# SCH_EasyEDA_OpenComs_ABP1_Front-panel_20.net
KiCad netlist of a schematic drawn in EasyEDA
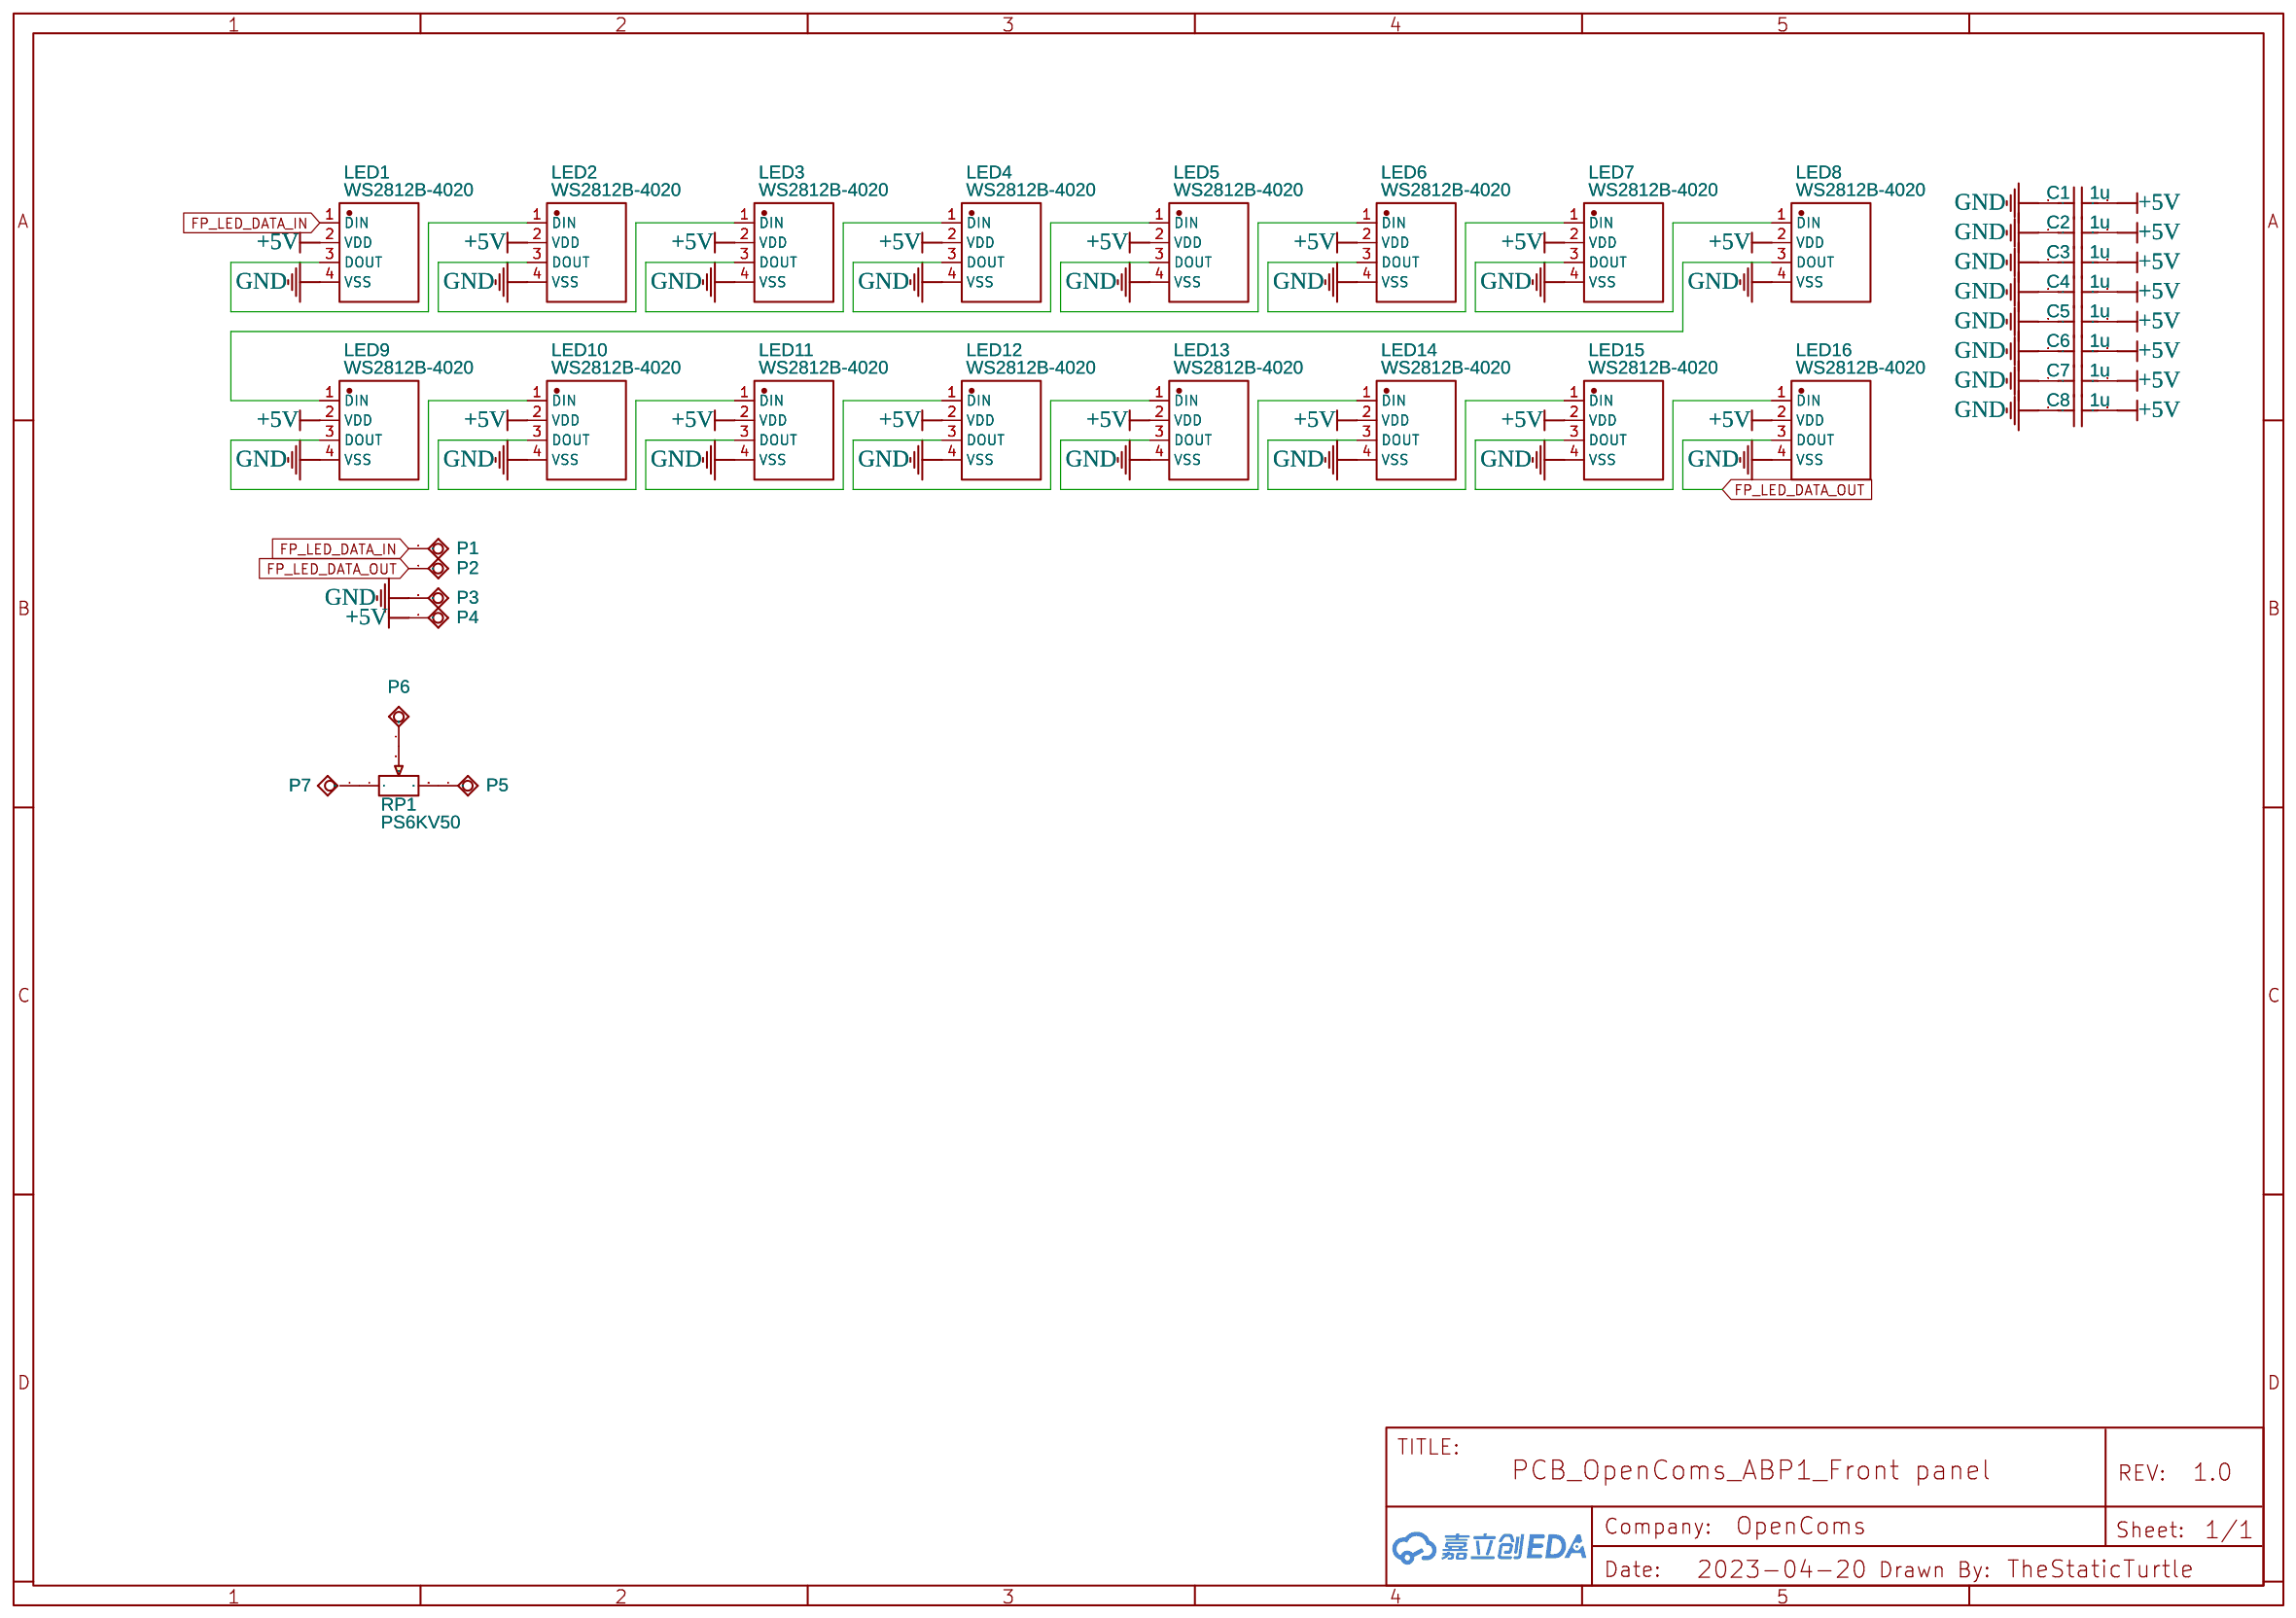
[diagram p0: schematic sheet]

(export (version "E")
  (design (tool "Eeschema 10.0.6"))
  (components
    (comp (ref "C1")
      (value "1u")
      (fields
        (field (name "BOM_Manufacturer Part") "CL21B105KBFNNNE")
        (field (name "BOM_Supplier Part") "C28323")
      )
      (libsource (lib "") (part "C_0805_US"))
    )
    (comp (ref "C2")
      (value "1u")
      (fields
        (field (name "BOM_Manufacturer Part") "CL21B105KBFNNNE")
        (field (name "BOM_Supplier Part") "C28323")
      )
      (libsource (lib "") (part "C_0805_US"))
    )
    (comp (ref "C3")
      (value "1u")
      (fields
        (field (name "BOM_Manufacturer Part") "CL21B105KBFNNNE")
        (field (name "BOM_Supplier Part") "C28323")
      )
      (libsource (lib "") (part "C_0805_US"))
    )
    (comp (ref "C4")
      (value "1u")
      (fields
        (field (name "BOM_Manufacturer Part") "CL21B105KBFNNNE")
        (field (name "BOM_Supplier Part") "C28323")
      )
      (libsource (lib "") (part "C_0805_US"))
    )
    (comp (ref "C5")
      (value "1u")
      (fields
        (field (name "BOM_Manufacturer Part") "CL21B105KBFNNNE")
        (field (name "BOM_Supplier Part") "C28323")
      )
      (libsource (lib "") (part "C_0805_US"))
    )
    (comp (ref "C6")
      (value "1u")
      (fields
        (field (name "BOM_Manufacturer Part") "CL21B105KBFNNNE")
        (field (name "BOM_Supplier Part") "C28323")
      )
      (libsource (lib "") (part "C_0805_US"))
    )
    (comp (ref "C7")
      (value "1u")
      (fields
        (field (name "BOM_Manufacturer Part") "CL21B105KBFNNNE")
        (field (name "BOM_Supplier Part") "C28323")
      )
      (libsource (lib "") (part "C_0805_US"))
    )
    (comp (ref "C8")
      (value "1u")
      (fields
        (field (name "BOM_Manufacturer Part") "CL21B105KBFNNNE")
        (field (name "BOM_Supplier Part") "C28323")
      )
      (libsource (lib "") (part "C_0805_US"))
    )
    (comp (ref "LED1")
      (value "WS2812B-4020")
      (fields (field (name "BOM_Supplier Part") "C965557"))
      (libsource (lib "") (part "WS2812B-4020"))
    )
    (comp (ref "LED2")
      (value "WS2812B-4020")
      (fields (field (name "BOM_Supplier Part") "C965557"))
      (libsource (lib "") (part "WS2812B-4020"))
    )
    (comp (ref "LED3")
      (value "WS2812B-4020")
      (fields (field (name "BOM_Supplier Part") "C965557"))
      (libsource (lib "") (part "WS2812B-4020"))
    )
    (comp (ref "LED4")
      (value "WS2812B-4020")
      (fields (field (name "BOM_Supplier Part") "C965557"))
      (libsource (lib "") (part "WS2812B-4020"))
    )
    (comp (ref "LED5")
      (value "WS2812B-4020")
      (fields (field (name "BOM_Supplier Part") "C965557"))
      (libsource (lib "") (part "WS2812B-4020"))
    )
    (comp (ref "LED6")
      (value "WS2812B-4020")
      (fields (field (name "BOM_Supplier Part") "C965557"))
      (libsource (lib "") (part "WS2812B-4020"))
    )
    (comp (ref "LED7")
      (value "WS2812B-4020")
      (fields (field (name "BOM_Supplier Part") "C965557"))
      (libsource (lib "") (part "WS2812B-4020"))
    )
    (comp (ref "LED8")
      (value "WS2812B-4020")
      (fields (field (name "BOM_Supplier Part") "C965557"))
      (libsource (lib "") (part "WS2812B-4020"))
    )
    (comp (ref "LED9")
      (value "WS2812B-4020")
      (fields (field (name "BOM_Supplier Part") "C965557"))
      (libsource (lib "") (part "WS2812B-4020"))
    )
    (comp (ref "LED10")
      (value "WS2812B-4020")
      (fields (field (name "BOM_Supplier Part") "C965557"))
      (libsource (lib "") (part "WS2812B-4020"))
    )
    (comp (ref "LED11")
      (value "WS2812B-4020")
      (fields (field (name "BOM_Supplier Part") "C965557"))
      (libsource (lib "") (part "WS2812B-4020"))
    )
    (comp (ref "LED12")
      (value "WS2812B-4020")
      (fields (field (name "BOM_Supplier Part") "C965557"))
      (libsource (lib "") (part "WS2812B-4020"))
    )
    (comp (ref "LED13")
      (value "WS2812B-4020")
      (fields (field (name "BOM_Supplier Part") "C965557"))
      (libsource (lib "") (part "WS2812B-4020"))
    )
    (comp (ref "LED14")
      (value "WS2812B-4020")
      (fields (field (name "BOM_Supplier Part") "C965557"))
      (libsource (lib "") (part "WS2812B-4020"))
    )
    (comp (ref "LED15")
      (value "WS2812B-4020")
      (fields (field (name "BOM_Supplier Part") "C965557"))
      (libsource (lib "") (part "WS2812B-4020"))
    )
    (comp (ref "LED16")
      (value "WS2812B-4020")
      (fields (field (name "BOM_Supplier Part") "C965557"))
      (libsource (lib "") (part "WS2812B-4020"))
    )
    (comp (ref "P1") (value "TESTPAD50") (libsource (lib "") (part "TESTPAD50")))
    (comp (ref "P2") (value "TESTPAD50") (libsource (lib "") (part "TESTPAD50")))
    (comp (ref "P3") (value "TESTPAD50") (libsource (lib "") (part "TESTPAD50")))
    (comp (ref "P4") (value "TESTPAD50") (libsource (lib "") (part "TESTPAD50")))
    (comp (ref "P5") (value "TESTPAD50") (libsource (lib "") (part "TESTPAD50")))
    (comp (ref "P6") (value "TESTPAD50") (libsource (lib "") (part "TESTPAD50_1")))
    (comp (ref "P7") (value "TESTPAD50") (libsource (lib "") (part "TESTPAD50_2")))
    (comp (ref "RP1")
      (value "PS6KV50")
      (fields
        (field (name "BOM_Manufacturer Part") "PS6KV50-103A3030-I-PM")
        (field (name "BOM_Supplier Part") "PS6KV50-103A-I-PM")
      )
      (libsource (lib "") (part "PS6KV50"))
    )
  )
  (nets
    (net (code "1") (name "+5V") (class "Default")
      (node (ref "C1") (pin "2") (pinfunction "2_2") (pintype "unspecified"))
      (node (ref "C2") (pin "2") (pinfunction "2_2") (pintype "unspecified"))
      (node (ref "C3") (pin "2") (pinfunction "2_2") (pintype "unspecified"))
      (node (ref "C4") (pin "2") (pinfunction "2_2") (pintype "unspecified"))
      (node (ref "C5") (pin "2") (pinfunction "2_2") (pintype "unspecified"))
      (node (ref "C6") (pin "2") (pinfunction "2_2") (pintype "unspecified"))
      (node (ref "C7") (pin "2") (pinfunction "2_2") (pintype "unspecified"))
      (node (ref "C8") (pin "2") (pinfunction "2_2") (pintype "unspecified"))
      (node (ref "LED1") (pin "2") (pinfunction "VDD_2") (pintype "unspecified"))
      (node (ref "LED10") (pin "2") (pinfunction "VDD_2") (pintype "unspecified"))
      (node (ref "LED11") (pin "2") (pinfunction "VDD_2") (pintype "unspecified"))
      (node (ref "LED12") (pin "2") (pinfunction "VDD_2") (pintype "unspecified"))
      (node (ref "LED13") (pin "2") (pinfunction "VDD_2") (pintype "unspecified"))
      (node (ref "LED14") (pin "2") (pinfunction "VDD_2") (pintype "unspecified"))
      (node (ref "LED15") (pin "2") (pinfunction "VDD_2") (pintype "unspecified"))
      (node (ref "LED16") (pin "2") (pinfunction "VDD_2") (pintype "unspecified"))
      (node (ref "LED2") (pin "2") (pinfunction "VDD_2") (pintype "unspecified"))
      (node (ref "LED3") (pin "2") (pinfunction "VDD_2") (pintype "unspecified"))
      (node (ref "LED4") (pin "2") (pinfunction "VDD_2") (pintype "unspecified"))
      (node (ref "LED5") (pin "2") (pinfunction "VDD_2") (pintype "unspecified"))
      (node (ref "LED6") (pin "2") (pinfunction "VDD_2") (pintype "unspecified"))
      (node (ref "LED7") (pin "2") (pinfunction "VDD_2") (pintype "unspecified"))
      (node (ref "LED8") (pin "2") (pinfunction "VDD_2") (pintype "unspecified"))
      (node (ref "LED9") (pin "2") (pinfunction "VDD_2") (pintype "unspecified"))
      (node (ref "P4") (pin "1") (pinfunction "PP_1") (pintype "bidirectional"))
    )
    (net (code "2") (name "FP_LED_DATA_IN") (class "Default")
      (node (ref "LED1") (pin "1") (pinfunction "DIN_1") (pintype "unspecified"))
      (node (ref "P1") (pin "1") (pinfunction "PP_1") (pintype "bidirectional"))
    )
    (net (code "3") (name "FP_LED_DATA_OUT") (class "Default")
      (node (ref "LED16") (pin "3") (pinfunction "DOUT_3") (pintype "unspecified"))
      (node (ref "P2") (pin "1") (pinfunction "PP_1") (pintype "bidirectional"))
    )
    (net (code "4") (name "GND") (class "Default")
      (node (ref "C1") (pin "1") (pinfunction "1_1") (pintype "unspecified"))
      (node (ref "C2") (pin "1") (pinfunction "1_1") (pintype "unspecified"))
      (node (ref "C3") (pin "1") (pinfunction "1_1") (pintype "unspecified"))
      (node (ref "C4") (pin "1") (pinfunction "1_1") (pintype "unspecified"))
      (node (ref "C5") (pin "1") (pinfunction "1_1") (pintype "unspecified"))
      (node (ref "C6") (pin "1") (pinfunction "1_1") (pintype "unspecified"))
      (node (ref "C7") (pin "1") (pinfunction "1_1") (pintype "unspecified"))
      (node (ref "C8") (pin "1") (pinfunction "1_1") (pintype "unspecified"))
      (node (ref "LED1") (pin "4") (pinfunction "VSS_4") (pintype "unspecified"))
      (node (ref "LED10") (pin "4") (pinfunction "VSS_4") (pintype "unspecified"))
      (node (ref "LED11") (pin "4") (pinfunction "VSS_4") (pintype "unspecified"))
      (node (ref "LED12") (pin "4") (pinfunction "VSS_4") (pintype "unspecified"))
      (node (ref "LED13") (pin "4") (pinfunction "VSS_4") (pintype "unspecified"))
      (node (ref "LED14") (pin "4") (pinfunction "VSS_4") (pintype "unspecified"))
      (node (ref "LED15") (pin "4") (pinfunction "VSS_4") (pintype "unspecified"))
      (node (ref "LED16") (pin "4") (pinfunction "VSS_4") (pintype "unspecified"))
      (node (ref "LED2") (pin "4") (pinfunction "VSS_4") (pintype "unspecified"))
      (node (ref "LED3") (pin "4") (pinfunction "VSS_4") (pintype "unspecified"))
      (node (ref "LED4") (pin "4") (pinfunction "VSS_4") (pintype "unspecified"))
      (node (ref "LED5") (pin "4") (pinfunction "VSS_4") (pintype "unspecified"))
      (node (ref "LED6") (pin "4") (pinfunction "VSS_4") (pintype "unspecified"))
      (node (ref "LED7") (pin "4") (pinfunction "VSS_4") (pintype "unspecified"))
      (node (ref "LED8") (pin "4") (pinfunction "VSS_4") (pintype "unspecified"))
      (node (ref "LED9") (pin "4") (pinfunction "VSS_4") (pintype "unspecified"))
      (node (ref "P3") (pin "1") (pinfunction "PP_1") (pintype "bidirectional"))
    )
    (net (code "5") (name "Net-(LED1-DOUT)") (class "Default")
      (node (ref "LED1") (pin "3") (pinfunction "DOUT_3") (pintype "unspecified"))
      (node (ref "LED2") (pin "1") (pinfunction "DIN_1") (pintype "unspecified"))
    )
    (net (code "6") (name "Net-(LED2-DOUT)") (class "Default")
      (node (ref "LED2") (pin "3") (pinfunction "DOUT_3") (pintype "unspecified"))
      (node (ref "LED3") (pin "1") (pinfunction "DIN_1") (pintype "unspecified"))
    )
    (net (code "7") (name "Net-(LED3-DOUT)") (class "Default")
      (node (ref "LED3") (pin "3") (pinfunction "DOUT_3") (pintype "unspecified"))
      (node (ref "LED4") (pin "1") (pinfunction "DIN_1") (pintype "unspecified"))
    )
    (net (code "8") (name "Net-(LED4-DOUT)") (class "Default")
      (node (ref "LED4") (pin "3") (pinfunction "DOUT_3") (pintype "unspecified"))
      (node (ref "LED5") (pin "1") (pinfunction "DIN_1") (pintype "unspecified"))
    )
    (net (code "9") (name "Net-(LED5-DOUT)") (class "Default")
      (node (ref "LED5") (pin "3") (pinfunction "DOUT_3") (pintype "unspecified"))
      (node (ref "LED6") (pin "1") (pinfunction "DIN_1") (pintype "unspecified"))
    )
    (net (code "10") (name "Net-(LED6-DOUT)") (class "Default")
      (node (ref "LED6") (pin "3") (pinfunction "DOUT_3") (pintype "unspecified"))
      (node (ref "LED7") (pin "1") (pinfunction "DIN_1") (pintype "unspecified"))
    )
    (net (code "11") (name "Net-(LED7-DOUT)") (class "Default")
      (node (ref "LED7") (pin "3") (pinfunction "DOUT_3") (pintype "unspecified"))
      (node (ref "LED8") (pin "1") (pinfunction "DIN_1") (pintype "unspecified"))
    )
    (net (code "12") (name "Net-(LED8-DOUT)") (class "Default")
      (node (ref "LED8") (pin "3") (pinfunction "DOUT_3") (pintype "unspecified"))
      (node (ref "LED9") (pin "1") (pinfunction "DIN_1") (pintype "unspecified"))
    )
    (net (code "13") (name "Net-(LED10-DIN)") (class "Default")
      (node (ref "LED10") (pin "1") (pinfunction "DIN_1") (pintype "unspecified"))
      (node (ref "LED9") (pin "3") (pinfunction "DOUT_3") (pintype "unspecified"))
    )
    (net (code "14") (name "Net-(LED10-DOUT)") (class "Default")
      (node (ref "LED10") (pin "3") (pinfunction "DOUT_3") (pintype "unspecified"))
      (node (ref "LED11") (pin "1") (pinfunction "DIN_1") (pintype "unspecified"))
    )
    (net (code "15") (name "Net-(LED11-DOUT)") (class "Default")
      (node (ref "LED11") (pin "3") (pinfunction "DOUT_3") (pintype "unspecified"))
      (node (ref "LED12") (pin "1") (pinfunction "DIN_1") (pintype "unspecified"))
    )
    (net (code "16") (name "Net-(LED12-DOUT)") (class "Default")
      (node (ref "LED12") (pin "3") (pinfunction "DOUT_3") (pintype "unspecified"))
      (node (ref "LED13") (pin "1") (pinfunction "DIN_1") (pintype "unspecified"))
    )
    (net (code "17") (name "Net-(LED13-DOUT)") (class "Default")
      (node (ref "LED13") (pin "3") (pinfunction "DOUT_3") (pintype "unspecified"))
      (node (ref "LED14") (pin "1") (pinfunction "DIN_1") (pintype "unspecified"))
    )
    (net (code "18") (name "Net-(LED14-DOUT)") (class "Default")
      (node (ref "LED14") (pin "3") (pinfunction "DOUT_3") (pintype "unspecified"))
      (node (ref "LED15") (pin "1") (pinfunction "DIN_1") (pintype "unspecified"))
    )
    (net (code "19") (name "Net-(LED15-DOUT)") (class "Default")
      (node (ref "LED15") (pin "3") (pinfunction "DOUT_3") (pintype "unspecified"))
      (node (ref "LED16") (pin "1") (pinfunction "DIN_1") (pintype "unspecified"))
    )
    (net (code "20") (name "Net-(P5-PP)") (class "Default")
      (node (ref "P5") (pin "1") (pinfunction "PP_1") (pintype "bidirectional"))
      (node (ref "RP1") (pin "3") (pinfunction "3_3") (pintype "input"))
    )
    (net (code "21") (name "Net-(P6-PP)") (class "Default")
      (node (ref "P6") (pin "1") (pinfunction "PP_1") (pintype "bidirectional"))
      (node (ref "RP1") (pin "2") (pinfunction "2_2") (pintype "input"))
    )
    (net (code "22") (name "Net-(P7-PP)") (class "Default")
      (node (ref "P7") (pin "1") (pinfunction "PP_1") (pintype "bidirectional"))
      (node (ref "RP1") (pin "1") (pinfunction "1_1") (pintype "input"))
    )
  )
)
